# PiMCU_Shield.net
KiCad netlist of a schematic drawn in EAGLE
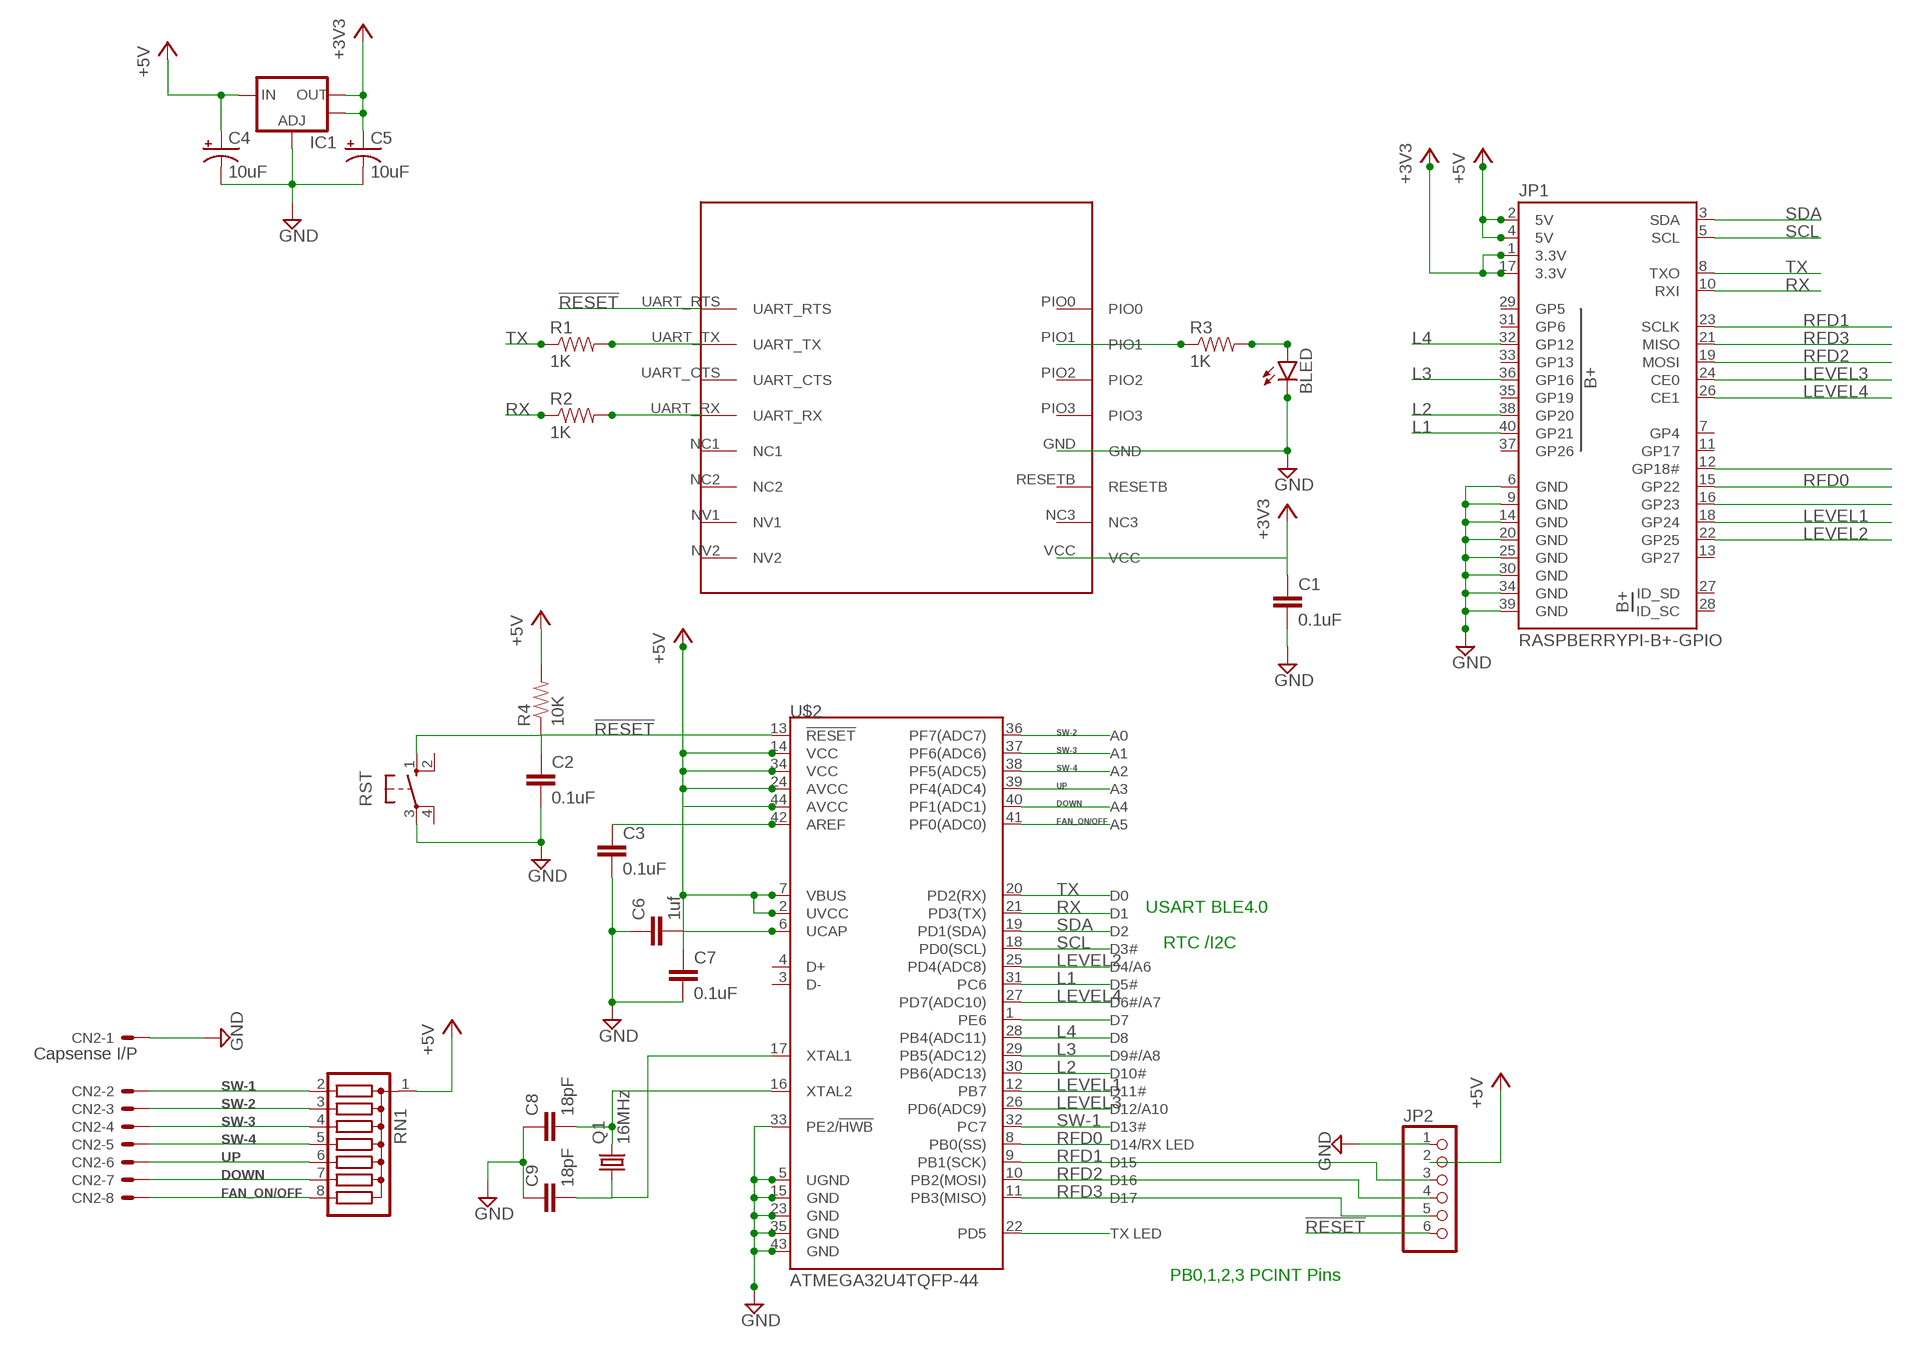
[diagram p0: schematic, sheet 1]

(export (version "E")
  (design (tool "Eeschema 10.0.6"))
  (components
    (comp (ref "BLED")
      (value "LED1206")
      (footprint "eagle-import:LED-1206")
      (libsource (lib "eagle-import") (part "LED1206"))
    )
    (comp (ref "C1")
      (value "0.1uF")
      (footprint "eagle-import:1206")
      (libsource (lib "eagle-import") (part "1.0UF50V10%(1206)"))
    )
    (comp (ref "C2")
      (value "0.1uF")
      (footprint "eagle-import:1206")
      (fields (field (name "PROD_ID") "CAP-09822"))
      (libsource (lib "eagle-import") (part "1.0UF50V10%(1206)"))
    )
    (comp (ref "C3")
      (value "0.1uF")
      (footprint "eagle-import:1206")
      (fields (field (name "PROD_ID") "CAP-09822"))
      (libsource (lib "eagle-import") (part "1.0UF50V10%(1206)"))
    )
    (comp (ref "C4")
      (value "10uF")
      (footprint "eagle-import:EIA3216")
      (libsource (lib "eagle-import") (part "10UF-16V-10%(TANT)"))
    )
    (comp (ref "C5")
      (value "10uF")
      (footprint "eagle-import:EIA3216")
      (libsource (lib "eagle-import") (part "10UF-16V-10%(TANT)"))
    )
    (comp (ref "C6")
      (value "1uf")
      (footprint "eagle-import:1206")
      (fields (field (name "PROD_ID") "CAP-09822"))
      (libsource (lib "eagle-import") (part "1.0UF50V10%(1206)"))
    )
    (comp (ref "C7")
      (value "0.1uF")
      (footprint "eagle-import:1206")
      (fields (field (name "PROD_ID") "CAP-09822"))
      (libsource (lib "eagle-import") (part "1.0UF50V10%(1206)"))
    )
    (comp (ref "C8")
      (value "18pF")
      (footprint "eagle-import:1206")
      (libsource (lib "eagle-import") (part "CAP1206"))
    )
    (comp (ref "C9")
      (value "18pF")
      (footprint "eagle-import:1206")
      (libsource (lib "eagle-import") (part "CAP1206"))
    )
    (comp (ref "CN2")
      (value "Capsense I/P")
      (footprint "eagle-import:22-23-2081")
      (fields (field (name "MF") "MOLEX") (field (name "MPN") "22-23-2081"))
      (libsource (lib "eagle-import") (part "22-23-2081"))
    )
    (comp (ref "IC1")
      (value "V_REG_LM1117SOT223")
      (footprint "eagle-import:SOT223")
      (libsource (lib "eagle-import") (part "V_REG_LM1117SOT223"))
    )
    (comp (ref "JP1")
      (value "RASPBERRYPI-B+-GPIO")
      (footprint "eagle-import:2X20-SHROUDED")
      (libsource (lib "eagle-import") (part "RASPBERRYPI-B+-GPIO"))
    )
    (comp (ref "JP2")
      (value "PINHD-1X6")
      (footprint "eagle-import:1X06")
      (libsource (lib "eagle-import") (part "PINHD-1X6"))
    )
    (comp (ref "Q1")
      (value "16MHz")
      (footprint "eagle-import:HC49UP")
      (libsource (lib "eagle-import") (part "CRYSTALHC49UP"))
    )
    (comp (ref "R1")
      (value "1K")
      (footprint "eagle-import:1206")
      (libsource (lib "eagle-import") (part "RESISTOR1206"))
    )
    (comp (ref "R2")
      (value "1K")
      (footprint "eagle-import:1206")
      (libsource (lib "eagle-import") (part "RESISTOR1206"))
    )
    (comp (ref "R3")
      (value "1K")
      (footprint "eagle-import:1206")
      (libsource (lib "eagle-import") (part "RESISTOR1206"))
    )
    (comp (ref "R4")
      (value "10K")
      (footprint "eagle-import:1206")
      (libsource (lib "eagle-import") (part "RESISTOR1206"))
    )
    (comp (ref "RN1")
      (value "G07R")
      (footprint "eagle-import:SIL8")
      (libsource (lib "eagle-import") (part "G07R"))
    )
    (comp (ref "RST")
      (value "10-XX")
      (footprint "eagle-import:B3F-10XX")
      (fields (field (name "MPN") "B3F-1000"))
      (libsource (lib "eagle-import") (part "10-XX"))
    )
    (comp (ref "U$1")
      (value "HM-11")
      (footprint "eagle-import:HM-11")
      (libsource (lib "eagle-import") (part "HM-11"))
    )
    (comp (ref "U$2")
      (value "ATMEGA32U4TQFP-44")
      (footprint "eagle-import:TQFP44")
      (libsource (lib "eagle-import") (part "ATMEGA32U4TQFP-44"))
    )
  )
  (nets
    (net (code "1") (name "+3V3") (class "Default")
      (node (ref "C1") (pin "1") (pinfunction "1_1") (pintype "passive"))
      (node (ref "C5") (pin "A") (pinfunction "+_A") (pintype "passive"))
      (node (ref "IC1") (pin "2") (pinfunction "OUT_2") (pintype "output"))
      (node (ref "IC1") (pin "4") (pinfunction "OUT_4") (pintype "output"))
      (node (ref "JP1") (pin "1") (pinfunction "3.3V_1") (pintype "power_in"))
      (node (ref "JP1") (pin "17") (pinfunction "3.3V_17") (pintype "power_in"))
      (node (ref "U$1") (pin "VCC") (pinfunction "VCC_VCC") (pintype "bidirectional"))
    )
    (net (code "2") (name "+5V") (class "Default")
      (node (ref "C4") (pin "A") (pinfunction "+_A") (pintype "passive"))
      (node (ref "C7") (pin "1") (pinfunction "1_1") (pintype "passive"))
      (node (ref "IC1") (pin "3") (pinfunction "IN_3") (pintype "input"))
      (node (ref "JP1") (pin "2") (pinfunction "5V_2") (pintype "power_in"))
      (node (ref "JP1") (pin "4") (pinfunction "5V_4") (pintype "power_in"))
      (node (ref "JP2") (pin "2") (pinfunction "2_2") (pintype "passive"))
      (node (ref "R4") (pin "2") (pinfunction "2_2") (pintype "passive"))
      (node (ref "RN1") (pin "1") (pinfunction "1_1") (pintype "passive"))
      (node (ref "U$2") (pin "14") (pinfunction "VCC_14") (pintype "bidirectional"))
      (node (ref "U$2") (pin "2") (pinfunction "UVCC_2") (pintype "bidirectional"))
      (node (ref "U$2") (pin "24") (pinfunction "AVCC_24") (pintype "bidirectional"))
      (node (ref "U$2") (pin "34") (pinfunction "VCC_34") (pintype "bidirectional"))
      (node (ref "U$2") (pin "44") (pinfunction "AVCC_44") (pintype "bidirectional"))
      (node (ref "U$2") (pin "7") (pinfunction "VBUS_7") (pintype "bidirectional"))
    )
    (net (code "3") (name "/DOWN") (class "Default")
      (node (ref "CN2") (pin "7") (pinfunction "S_7") (pintype "passive"))
      (node (ref "RN1") (pin "7") (pinfunction "7_7") (pintype "passive"))
      (node (ref "U$2") (pin "40") (pinfunction "PF1(ADC1)_40") (pintype "bidirectional"))
    )
    (net (code "4") (name "/FAN_ON{slash}OFF") (class "Default")
      (node (ref "CN2") (pin "8") (pinfunction "S_8") (pintype "passive"))
      (node (ref "RN1") (pin "8") (pinfunction "8_8") (pintype "passive"))
      (node (ref "U$2") (pin "41") (pinfunction "PF0(ADC0)_41") (pintype "bidirectional"))
    )
    (net (code "5") (name "/L1") (class "Default")
      (node (ref "JP1") (pin "40") (pinfunction "GP21_40") (pintype "bidirectional"))
      (node (ref "U$2") (pin "31") (pinfunction "PC6_31") (pintype "bidirectional"))
    )
    (net (code "6") (name "/L2") (class "Default")
      (node (ref "JP1") (pin "38") (pinfunction "GP20_38") (pintype "bidirectional"))
      (node (ref "U$2") (pin "30") (pinfunction "PB6(ADC13)_30") (pintype "bidirectional"))
    )
    (net (code "7") (name "/L3") (class "Default")
      (node (ref "JP1") (pin "36") (pinfunction "GP16_36") (pintype "bidirectional"))
      (node (ref "U$2") (pin "29") (pinfunction "PB5(ADC12)_29") (pintype "bidirectional"))
    )
    (net (code "8") (name "/L4") (class "Default")
      (node (ref "JP1") (pin "32") (pinfunction "GP12_32") (pintype "bidirectional"))
      (node (ref "U$2") (pin "28") (pinfunction "PB4(ADC11)_28") (pintype "bidirectional"))
    )
    (net (code "9") (name "/LEVEL1") (class "Default")
      (node (ref "JP1") (pin "18") (pinfunction "GP24_18") (pintype "bidirectional"))
      (node (ref "U$2") (pin "12") (pinfunction "PB7_12") (pintype "bidirectional"))
    )
    (net (code "10") (name "/LEVEL2") (class "Default")
      (node (ref "JP1") (pin "22") (pinfunction "GP25_22") (pintype "bidirectional"))
      (node (ref "U$2") (pin "25") (pinfunction "PD4(ADC8)_25") (pintype "bidirectional"))
    )
    (net (code "11") (name "/LEVEL3") (class "Default")
      (node (ref "JP1") (pin "24") (pinfunction "CE0_24") (pintype "output"))
      (node (ref "U$2") (pin "26") (pinfunction "PD6(ADC9)_26") (pintype "bidirectional"))
    )
    (net (code "12") (name "/LEVEL4") (class "Default")
      (node (ref "JP1") (pin "26") (pinfunction "CE1_26") (pintype "output"))
      (node (ref "U$2") (pin "27") (pinfunction "PD7(ADC10)_27") (pintype "bidirectional"))
    )
    (net (code "13") (name "/RFD0") (class "Default")
      (node (ref "JP1") (pin "15") (pinfunction "GP22_15") (pintype "bidirectional"))
      (node (ref "U$2") (pin "8") (pinfunction "PB0(SS)_8") (pintype "bidirectional"))
    )
    (net (code "14") (name "/RFD1") (class "Default")
      (node (ref "JP1") (pin "23") (pinfunction "SCLK_23") (pintype "output"))
      (node (ref "JP2") (pin "3") (pinfunction "3_3") (pintype "passive"))
      (node (ref "U$2") (pin "9") (pinfunction "PB1(SCK)_9") (pintype "bidirectional"))
    )
    (net (code "15") (name "/RFD2") (class "Default")
      (node (ref "JP1") (pin "19") (pinfunction "MOSI_19") (pintype "output"))
      (node (ref "JP2") (pin "4") (pinfunction "4_4") (pintype "passive"))
      (node (ref "U$2") (pin "10") (pinfunction "PB2(MOSI)_10") (pintype "bidirectional"))
    )
    (net (code "16") (name "/RFD3") (class "Default")
      (node (ref "JP1") (pin "21") (pinfunction "MISO_21") (pintype "input"))
      (node (ref "JP2") (pin "5") (pinfunction "5_5") (pintype "passive"))
      (node (ref "U$2") (pin "11") (pinfunction "PB3(MISO)_11") (pintype "bidirectional"))
    )
    (net (code "17") (name "/RX") (class "Default")
      (node (ref "JP1") (pin "10") (pinfunction "RXI_10") (pintype "input"))
      (node (ref "R2") (pin "1") (pinfunction "1_1") (pintype "passive"))
      (node (ref "U$2") (pin "21") (pinfunction "PD3(TX)_21") (pintype "bidirectional"))
    )
    (net (code "18") (name "/SCL") (class "Default")
      (node (ref "JP1") (pin "5") (pinfunction "SCL_5") (pintype "bidirectional"))
      (node (ref "U$2") (pin "18") (pinfunction "PD0(SCL)_18") (pintype "bidirectional"))
    )
    (net (code "19") (name "/SDA") (class "Default")
      (node (ref "JP1") (pin "3") (pinfunction "SDA_3") (pintype "bidirectional"))
      (node (ref "U$2") (pin "19") (pinfunction "PD1(SDA)_19") (pintype "bidirectional"))
    )
    (net (code "20") (name "/SW-1") (class "Default")
      (node (ref "CN2") (pin "2") (pinfunction "S_2") (pintype "passive"))
      (node (ref "RN1") (pin "2") (pinfunction "2_2") (pintype "passive"))
      (node (ref "U$2") (pin "32") (pinfunction "PC7_32") (pintype "bidirectional"))
    )
    (net (code "21") (name "/SW-2") (class "Default")
      (node (ref "CN2") (pin "3") (pinfunction "S_3") (pintype "passive"))
      (node (ref "RN1") (pin "3") (pinfunction "3_3") (pintype "passive"))
      (node (ref "U$2") (pin "36") (pinfunction "PF7(ADC7)_36") (pintype "bidirectional"))
    )
    (net (code "22") (name "/SW-3") (class "Default")
      (node (ref "CN2") (pin "4") (pinfunction "S_4") (pintype "passive"))
      (node (ref "RN1") (pin "4") (pinfunction "4_4") (pintype "passive"))
      (node (ref "U$2") (pin "37") (pinfunction "PF6(ADC6)_37") (pintype "bidirectional"))
    )
    (net (code "23") (name "/SW-4") (class "Default")
      (node (ref "CN2") (pin "5") (pinfunction "S_5") (pintype "passive"))
      (node (ref "RN1") (pin "5") (pinfunction "5_5") (pintype "passive"))
      (node (ref "U$2") (pin "38") (pinfunction "PF5(ADC5)_38") (pintype "bidirectional"))
    )
    (net (code "24") (name "/TX") (class "Default")
      (node (ref "JP1") (pin "8") (pinfunction "TXO_8") (pintype "output"))
      (node (ref "R1") (pin "1") (pinfunction "1_1") (pintype "passive"))
      (node (ref "U$2") (pin "20") (pinfunction "PD2(RX)_20") (pintype "bidirectional"))
    )
    (net (code "25") (name "/UP") (class "Default")
      (node (ref "CN2") (pin "6") (pinfunction "S_6") (pintype "passive"))
      (node (ref "RN1") (pin "6") (pinfunction "6_6") (pintype "passive"))
      (node (ref "U$2") (pin "39") (pinfunction "PF4(ADC4)_39") (pintype "bidirectional"))
    )
    (net (code "26") (name "/~{RESET}") (class "Default")
      (node (ref "C2") (pin "1") (pinfunction "1_1") (pintype "passive"))
      (node (ref "JP2") (pin "6") (pinfunction "6_6") (pintype "passive"))
      (node (ref "R4") (pin "1") (pinfunction "1_1") (pintype "passive"))
      (node (ref "RST") (pin "1") (pinfunction "S_1") (pintype "passive"))
      (node (ref "U$1") (pin "UART_RTS") (pinfunction "UART_RTS_UART_RTS") (pintype "bidirectional"))
      (node (ref "U$2") (pin "13") (pinfunction "~{RESET}_13") (pintype "bidirectional"))
    )
    (net (code "27") (name "GND") (class "Default")
      (node (ref "BLED") (pin "C") (pinfunction "C_C") (pintype "passive"))
      (node (ref "C1") (pin "2") (pinfunction "2_2") (pintype "passive"))
      (node (ref "C2") (pin "2") (pinfunction "2_2") (pintype "passive"))
      (node (ref "C3") (pin "2") (pinfunction "2_2") (pintype "passive"))
      (node (ref "C4") (pin "C") (pinfunction "-_C") (pintype "passive"))
      (node (ref "C5") (pin "C") (pinfunction "-_C") (pintype "passive"))
      (node (ref "C6") (pin "1") (pinfunction "1_1") (pintype "passive"))
      (node (ref "C7") (pin "2") (pinfunction "2_2") (pintype "passive"))
      (node (ref "C8") (pin "1") (pinfunction "1_1") (pintype "passive"))
      (node (ref "C9") (pin "1") (pinfunction "1_1") (pintype "passive"))
      (node (ref "CN2") (pin "1") (pinfunction "S_1") (pintype "passive"))
      (node (ref "IC1") (pin "1") (pinfunction "ADJ_1") (pintype "input"))
      (node (ref "JP1") (pin "14") (pinfunction "GND_14") (pintype "power_in"))
      (node (ref "JP1") (pin "20") (pinfunction "GND_20") (pintype "power_in"))
      (node (ref "JP1") (pin "25") (pinfunction "GND_25") (pintype "power_in"))
      (node (ref "JP1") (pin "30") (pinfunction "GND_30") (pintype "power_in"))
      (node (ref "JP1") (pin "34") (pinfunction "GND_34") (pintype "power_in"))
      (node (ref "JP1") (pin "39") (pinfunction "GND_39") (pintype "power_in"))
      (node (ref "JP1") (pin "6") (pinfunction "GND_6") (pintype "power_in"))
      (node (ref "JP1") (pin "9") (pinfunction "GND_9") (pintype "power_in"))
      (node (ref "JP2") (pin "1") (pinfunction "1_1") (pintype "passive"))
      (node (ref "RST") (pin "3") (pinfunction "P_3") (pintype "passive"))
      (node (ref "U$1") (pin "GND") (pinfunction "GND_GND") (pintype "bidirectional"))
      (node (ref "U$2") (pin "15") (pinfunction "GND_15") (pintype "bidirectional"))
      (node (ref "U$2") (pin "23") (pinfunction "GND_23") (pintype "bidirectional"))
      (node (ref "U$2") (pin "33") (pinfunction "PE2/~{HWB}_33") (pintype "bidirectional"))
      (node (ref "U$2") (pin "35") (pinfunction "GND_35") (pintype "bidirectional"))
      (node (ref "U$2") (pin "43") (pinfunction "GND_43") (pintype "bidirectional"))
      (node (ref "U$2") (pin "5") (pinfunction "UGND_5") (pintype "bidirectional"))
    )
    (net (code "28") (name "Net-(BLED-PadA)") (class "Default")
      (node (ref "BLED") (pin "A") (pinfunction "A_A") (pintype "passive"))
      (node (ref "R3") (pin "2") (pinfunction "2_2") (pintype "passive"))
    )
    (net (code "29") (name "Net-(R1-Pad2)") (class "Default")
      (node (ref "R1") (pin "2") (pinfunction "2_2") (pintype "passive"))
      (node (ref "U$1") (pin "UART_TX") (pinfunction "UART_TX_UART_TX") (pintype "bidirectional"))
    )
    (net (code "30") (name "Net-(R2-Pad2)") (class "Default")
      (node (ref "R2") (pin "2") (pinfunction "2_2") (pintype "passive"))
      (node (ref "U$1") (pin "UART_RX") (pinfunction "UART_RX_UART_RX") (pintype "bidirectional"))
    )
    (net (code "31") (name "Net-(R3-Pad1)") (class "Default")
      (node (ref "R3") (pin "1") (pinfunction "1_1") (pintype "passive"))
      (node (ref "U$1") (pin "PIO1") (pinfunction "PIO1_PIO1") (pintype "bidirectional"))
    )
    (net (code "32") (name "Net-(U$2-AREF)") (class "Default")
      (node (ref "C3") (pin "1") (pinfunction "1_1") (pintype "passive"))
      (node (ref "U$2") (pin "42") (pinfunction "AREF_42") (pintype "bidirectional"))
    )
    (net (code "33") (name "Net-(U$2-UCAP)") (class "Default")
      (node (ref "C6") (pin "2") (pinfunction "2_2") (pintype "passive"))
      (node (ref "U$2") (pin "6") (pinfunction "UCAP_6") (pintype "bidirectional"))
    )
    (net (code "34") (name "Net-(U$2-XTAL1)") (class "Default")
      (node (ref "C9") (pin "2") (pinfunction "2_2") (pintype "passive"))
      (node (ref "Q1") (pin "1") (pinfunction "1_1") (pintype "passive"))
      (node (ref "U$2") (pin "17") (pinfunction "XTAL1_17") (pintype "bidirectional"))
    )
    (net (code "35") (name "Net-(U$2-XTAL2)") (class "Default")
      (node (ref "C8") (pin "2") (pinfunction "2_2") (pintype "passive"))
      (node (ref "Q1") (pin "2") (pinfunction "2_2") (pintype "passive"))
      (node (ref "U$2") (pin "16") (pinfunction "XTAL2_16") (pintype "bidirectional"))
    )
    (net (code "36") (name "unconnected-(JP1-GP4-Pad7)") (class "Default")
      (node (ref "JP1") (pin "7") (pinfunction "GP4_7") (pintype "bidirectional"))
    )
    (net (code "37") (name "unconnected-(JP1-GP5-Pad29)") (class "Default")
      (node (ref "JP1") (pin "29") (pinfunction "GP5_29") (pintype "bidirectional"))
    )
    (net (code "38") (name "unconnected-(JP1-GP6-Pad31)") (class "Default")
      (node (ref "JP1") (pin "31") (pinfunction "GP6_31") (pintype "bidirectional"))
    )
    (net (code "39") (name "unconnected-(JP1-GP13-Pad33)") (class "Default")
      (node (ref "JP1") (pin "33") (pinfunction "GP13_33") (pintype "bidirectional"))
    )
    (net (code "40") (name "unconnected-(JP1-GP17-Pad11)") (class "Default")
      (node (ref "JP1") (pin "11") (pinfunction "GP17_11") (pintype "bidirectional"))
    )
    (net (code "41") (name "unconnected-(JP1-GP18#-Pad12)") (class "Default")
      (node (ref "JP1") (pin "12") (pinfunction "GP18#_12") (pintype "bidirectional"))
    )
    (net (code "42") (name "unconnected-(JP1-GP19-Pad35)") (class "Default")
      (node (ref "JP1") (pin "35") (pinfunction "GP19_35") (pintype "bidirectional"))
    )
    (net (code "43") (name "unconnected-(JP1-GP23-Pad16)") (class "Default")
      (node (ref "JP1") (pin "16") (pinfunction "GP23_16") (pintype "bidirectional"))
    )
    (net (code "44") (name "unconnected-(JP1-GP26-Pad37)") (class "Default")
      (node (ref "JP1") (pin "37") (pinfunction "GP26_37") (pintype "bidirectional"))
    )
    (net (code "45") (name "unconnected-(JP1-GP27-Pad13)") (class "Default")
      (node (ref "JP1") (pin "13") (pinfunction "GP27_13") (pintype "bidirectional"))
    )
    (net (code "46") (name "unconnected-(JP1-ID_SC-Pad28)") (class "Default")
      (node (ref "JP1") (pin "28") (pinfunction "ID_SC_28") (pintype "bidirectional"))
    )
    (net (code "47") (name "unconnected-(JP1-ID_SD-Pad27)") (class "Default")
      (node (ref "JP1") (pin "27") (pinfunction "ID_SD_27") (pintype "bidirectional"))
    )
    (net (code "48") (name "unconnected-(RST-P1-Pad4)") (class "Default")
      (node (ref "RST") (pin "4") (pinfunction "P1_4") (pintype "passive"))
    )
    (net (code "49") (name "unconnected-(RST-S1-Pad2)") (class "Default")
      (node (ref "RST") (pin "2") (pinfunction "S1_2") (pintype "passive"))
    )
    (net (code "50") (name "unconnected-(U$1-PadNC1)") (class "Default")
      (node (ref "U$1") (pin "NC1") (pinfunction "NC1_NC1") (pintype "bidirectional"))
    )
    (net (code "51") (name "unconnected-(U$1-PadNC2)") (class "Default")
      (node (ref "U$1") (pin "NC2") (pinfunction "NC2_NC2") (pintype "bidirectional"))
    )
    (net (code "52") (name "unconnected-(U$1-PadNC3)") (class "Default")
      (node (ref "U$1") (pin "NC3") (pinfunction "NC3_NC3") (pintype "bidirectional"))
    )
    (net (code "53") (name "unconnected-(U$1-PadNV1)") (class "Default")
      (node (ref "U$1") (pin "NV1") (pinfunction "NV1_NV1") (pintype "bidirectional"))
    )
    (net (code "54") (name "unconnected-(U$1-PadNV2)") (class "Default")
      (node (ref "U$1") (pin "NV2") (pinfunction "NV2_NV2") (pintype "bidirectional"))
    )
    (net (code "55") (name "unconnected-(U$1-PadPIO0)") (class "Default")
      (node (ref "U$1") (pin "PIO0") (pinfunction "PIO0_PIO0") (pintype "bidirectional"))
    )
    (net (code "56") (name "unconnected-(U$1-PadPIO2)") (class "Default")
      (node (ref "U$1") (pin "PIO2") (pinfunction "PIO2_PIO2") (pintype "bidirectional"))
    )
    (net (code "57") (name "unconnected-(U$1-PadPIO3)") (class "Default")
      (node (ref "U$1") (pin "PIO3") (pinfunction "PIO3_PIO3") (pintype "bidirectional"))
    )
    (net (code "58") (name "unconnected-(U$1-PadRESETB)") (class "Default")
      (node (ref "U$1") (pin "RESETB") (pinfunction "RESETB_RESETB") (pintype "bidirectional"))
    )
    (net (code "59") (name "unconnected-(U$1-PadUART_CTS)") (class "Default")
      (node (ref "U$1") (pin "UART_CTS") (pinfunction "UART_CTS_UART_CTS") (pintype "bidirectional"))
    )
    (net (code "60") (name "unconnected-(U$2-D+-Pad4)") (class "Default")
      (node (ref "U$2") (pin "4") (pinfunction "D+_4") (pintype "bidirectional"))
    )
    (net (code "61") (name "unconnected-(U$2-D--Pad3)") (class "Default")
      (node (ref "U$2") (pin "3") (pinfunction "D-_3") (pintype "bidirectional"))
    )
    (net (code "62") (name "unconnected-(U$2-PD5-Pad22)") (class "Default")
      (node (ref "U$2") (pin "22") (pinfunction "PD5_22") (pintype "bidirectional"))
    )
    (net (code "63") (name "unconnected-(U$2-PE6-Pad1)") (class "Default")
      (node (ref "U$2") (pin "1") (pinfunction "PE6_1") (pintype "bidirectional"))
    )
  )
)
